# br__pl_power_adapter.net
KiCad netlist of a schematic drawn in Altium Designer
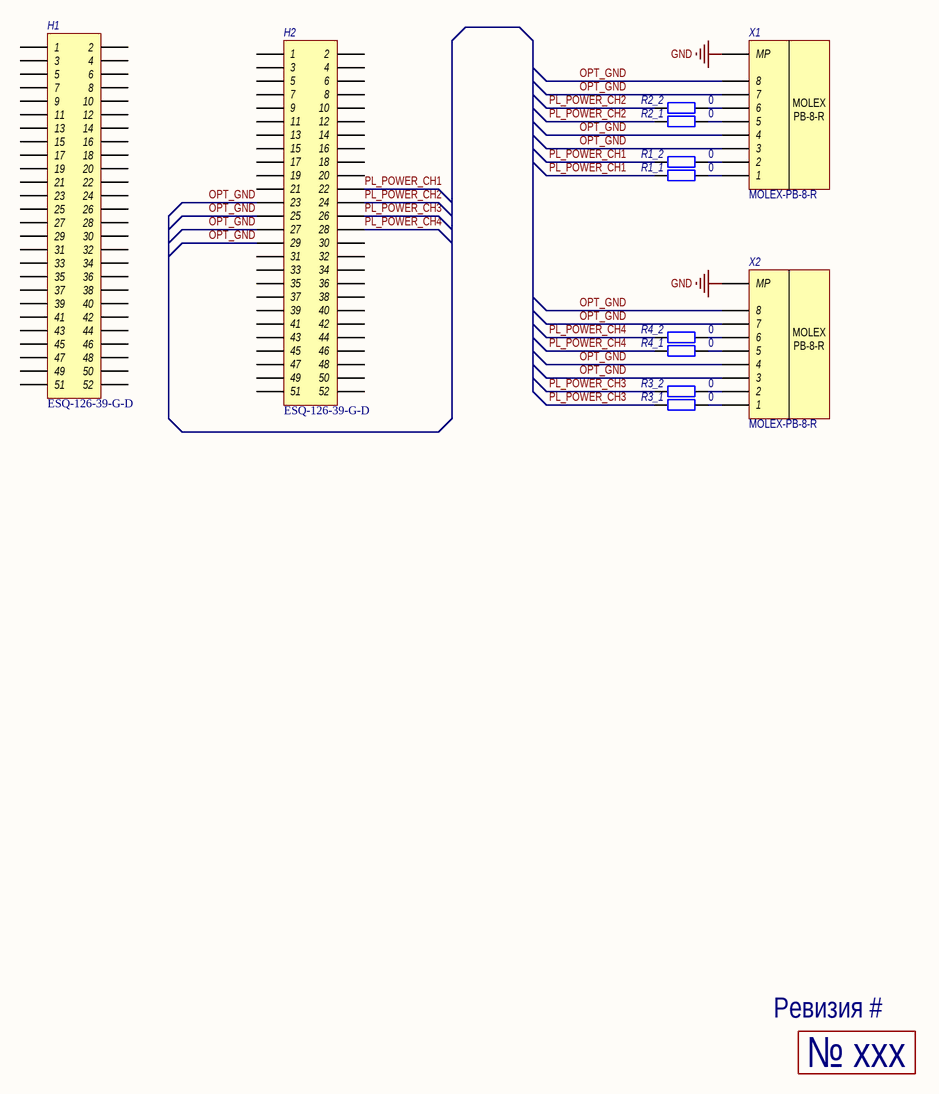
[diagram p0: brс_pl_power_adapter.SchDoc]

(export (version "E")
  (design (tool "Eeschema 10.0.6"))
  (components
    (comp (ref "H1")
      (value "ESQ-126-39-G-D")
      (footprint "ESQ-126-39-G-D")
      (description "Elevated socket, dual-row, 26-pin per row")
      (libsource (lib "ESQ-126-39-G-D") (part "ESQ-126-39-G-D"))
    )
    (comp (ref "H2")
      (value "ESQ-126-39-G-D")
      (footprint "ESQ-126-39-G-D")
      (description "Elevated socket, dual-row, 26-pin per row")
      (libsource (lib "ESQ-126-39-G-D") (part "ESQ-126-39-G-D"))
    )
    (comp (ref "R1_1")
      (value "0")
      (footprint "SMD_0805")
      (description "Resistor")
      (fields (field (name "Comment") "OSM R1-12"))
      (libsource (lib "altium-import") (part "root_0_Resistor_"))
    )
    (comp (ref "R1_2")
      (value "0")
      (footprint "SMD_0805")
      (description "Resistor")
      (fields (field (name "Comment") "OSM R1-12"))
      (libsource (lib "altium-import") (part "root_0_Resistor_"))
    )
    (comp (ref "R2_1")
      (value "0")
      (footprint "SMD_0805")
      (description "Resistor")
      (fields (field (name "Comment") "OSM R1-12"))
      (libsource (lib "altium-import") (part "root_0_Resistor_"))
    )
    (comp (ref "R2_2")
      (value "0")
      (footprint "SMD_0805")
      (description "Resistor")
      (fields (field (name "Comment") "OSM R1-12"))
      (libsource (lib "altium-import") (part "root_0_Resistor_"))
    )
    (comp (ref "R3_1")
      (value "0")
      (footprint "SMD_0805")
      (description "Resistor")
      (fields (field (name "Comment") "OSM R1-12"))
      (libsource (lib "altium-import") (part "root_0_Resistor_"))
    )
    (comp (ref "R3_2")
      (value "0")
      (footprint "SMD_0805")
      (description "Resistor")
      (fields (field (name "Comment") "OSM R1-12"))
      (libsource (lib "altium-import") (part "root_0_Resistor_"))
    )
    (comp (ref "R4_1")
      (value "0")
      (footprint "SMD_0805")
      (description "Resistor")
      (fields (field (name "Comment") "OSM R1-12"))
      (libsource (lib "altium-import") (part "root_0_Resistor_"))
    )
    (comp (ref "R4_2")
      (value "0")
      (footprint "SMD_0805")
      (description "Resistor")
      (fields (field (name "Comment") "OSM R1-12"))
      (libsource (lib "altium-import") (part "root_0_Resistor_"))
    )
    (comp (ref "SN")
      (value "Место под нанесение серийного номера")
      (footprint "Serial_number_v3")
      (libsource (lib "altium-import") (part "root_0_Serial_number_"))
    )
    (comp (ref "X1")
      (value "MOLEX-PB-8")
      (footprint "MOLEX-PB-8-R")
      (description "MOLEX PicoBlade 8-pin")
      (fields (field (name "НАИМЕНОВАНИЕ") "MOLEX-PB-8-R"))
      (libsource (lib "Molex-PB-8") (part "MOLEX-PB-8"))
    )
    (comp (ref "X2")
      (value "MOLEX-PB-8")
      (footprint "MOLEX-PB-8-R")
      (description "MOLEX PicoBlade 8-pin")
      (fields (field (name "НАИМЕНОВАНИЕ") "MOLEX-PB-8-R"))
      (libsource (lib "Molex-PB-8") (part "MOLEX-PB-8"))
    )
  )
  (nets
    (net (code "1") (name "/OPT_GND") (class "Default")
      (node (ref "H2") (pin "23") (pinfunction "23_23") (pintype "passive"))
      (node (ref "H2") (pin "25") (pinfunction "25_25") (pintype "passive"))
      (node (ref "H2") (pin "27") (pinfunction "27_27") (pintype "passive"))
      (node (ref "H2") (pin "29") (pinfunction "29_29") (pintype "passive"))
      (node (ref "X1") (pin "3") (pinfunction "3_3") (pintype "passive"))
      (node (ref "X1") (pin "4") (pinfunction "4_4") (pintype "passive"))
      (node (ref "X1") (pin "7") (pinfunction "7_7") (pintype "passive"))
      (node (ref "X1") (pin "8") (pinfunction "8_8") (pintype "passive"))
      (node (ref "X2") (pin "3") (pinfunction "3_3") (pintype "passive"))
      (node (ref "X2") (pin "4") (pinfunction "4_4") (pintype "passive"))
      (node (ref "X2") (pin "7") (pinfunction "7_7") (pintype "passive"))
      (node (ref "X2") (pin "8") (pinfunction "8_8") (pintype "passive"))
    )
    (net (code "2") (name "/PL_POWER_CH1") (class "Default")
      (node (ref "H2") (pin "22") (pinfunction "22_22") (pintype "passive"))
      (node (ref "R1_1") (pin "1") (pinfunction "1_1") (pintype "passive"))
      (node (ref "R1_2") (pin "1") (pinfunction "1_1") (pintype "passive"))
    )
    (net (code "3") (name "/PL_POWER_CH2") (class "Default")
      (node (ref "H2") (pin "24") (pinfunction "24_24") (pintype "passive"))
      (node (ref "R2_1") (pin "1") (pinfunction "1_1") (pintype "passive"))
      (node (ref "R2_2") (pin "1") (pinfunction "1_1") (pintype "passive"))
    )
    (net (code "4") (name "/PL_POWER_CH3") (class "Default")
      (node (ref "H2") (pin "26") (pinfunction "26_26") (pintype "passive"))
      (node (ref "R3_1") (pin "1") (pinfunction "1_1") (pintype "passive"))
      (node (ref "R3_2") (pin "1") (pinfunction "1_1") (pintype "passive"))
    )
    (net (code "5") (name "/PL_POWER_CH4") (class "Default")
      (node (ref "H2") (pin "28") (pinfunction "28_28") (pintype "passive"))
      (node (ref "R4_1") (pin "1") (pinfunction "1_1") (pintype "passive"))
      (node (ref "R4_2") (pin "1") (pinfunction "1_1") (pintype "passive"))
    )
    (net (code "6") (name "GND") (class "Default")
      (node (ref "X1") (pin "MP") (pinfunction "MP_MP") (pintype "passive"))
      (node (ref "X2") (pin "MP") (pinfunction "MP_MP") (pintype "passive"))
    )
    (net (code "7") (name "Net-(R1_1-Pad2)") (class "Default")
      (node (ref "R1_1") (pin "2") (pinfunction "2_2") (pintype "passive"))
      (node (ref "X1") (pin "1") (pinfunction "1_1") (pintype "passive"))
    )
    (net (code "8") (name "Net-(R1_2-Pad2)") (class "Default")
      (node (ref "R1_2") (pin "2") (pinfunction "2_2") (pintype "passive"))
      (node (ref "X1") (pin "2") (pinfunction "2_2") (pintype "passive"))
    )
    (net (code "9") (name "Net-(R2_1-Pad2)") (class "Default")
      (node (ref "R2_1") (pin "2") (pinfunction "2_2") (pintype "passive"))
      (node (ref "X1") (pin "5") (pinfunction "5_5") (pintype "passive"))
    )
    (net (code "10") (name "Net-(R2_2-Pad2)") (class "Default")
      (node (ref "R2_2") (pin "2") (pinfunction "2_2") (pintype "passive"))
      (node (ref "X1") (pin "6") (pinfunction "6_6") (pintype "passive"))
    )
    (net (code "11") (name "Net-(R3_1-Pad2)") (class "Default")
      (node (ref "R3_1") (pin "2") (pinfunction "2_2") (pintype "passive"))
      (node (ref "X2") (pin "1") (pinfunction "1_1") (pintype "passive"))
    )
    (net (code "12") (name "Net-(R3_2-Pad2)") (class "Default")
      (node (ref "R3_2") (pin "2") (pinfunction "2_2") (pintype "passive"))
      (node (ref "X2") (pin "2") (pinfunction "2_2") (pintype "passive"))
    )
    (net (code "13") (name "Net-(R4_1-Pad2)") (class "Default")
      (node (ref "R4_1") (pin "2") (pinfunction "2_2") (pintype "passive"))
      (node (ref "X2") (pin "5") (pinfunction "5_5") (pintype "passive"))
    )
    (net (code "14") (name "Net-(R4_2-Pad2)") (class "Default")
      (node (ref "R4_2") (pin "2") (pinfunction "2_2") (pintype "passive"))
      (node (ref "X2") (pin "6") (pinfunction "6_6") (pintype "passive"))
    )
    (net (code "15") (name "unconnected-(H1-Pad1)") (class "Default")
      (node (ref "H1") (pin "1") (pinfunction "1_1") (pintype "passive"))
    )
    (net (code "16") (name "unconnected-(H1-Pad2)") (class "Default")
      (node (ref "H1") (pin "2") (pinfunction "2_2") (pintype "passive"))
    )
    (net (code "17") (name "unconnected-(H1-Pad3)") (class "Default")
      (node (ref "H1") (pin "3") (pinfunction "3_3") (pintype "passive"))
    )
    (net (code "18") (name "unconnected-(H1-Pad4)") (class "Default")
      (node (ref "H1") (pin "4") (pinfunction "4_4") (pintype "passive"))
    )
    (net (code "19") (name "unconnected-(H1-Pad5)") (class "Default")
      (node (ref "H1") (pin "5") (pinfunction "5_5") (pintype "passive"))
    )
    (net (code "20") (name "unconnected-(H1-Pad6)") (class "Default")
      (node (ref "H1") (pin "6") (pinfunction "6_6") (pintype "passive"))
    )
    (net (code "21") (name "unconnected-(H1-Pad7)") (class "Default")
      (node (ref "H1") (pin "7") (pinfunction "7_7") (pintype "passive"))
    )
    (net (code "22") (name "unconnected-(H1-Pad8)") (class "Default")
      (node (ref "H1") (pin "8") (pinfunction "8_8") (pintype "passive"))
    )
    (net (code "23") (name "unconnected-(H1-Pad9)") (class "Default")
      (node (ref "H1") (pin "9") (pinfunction "9_9") (pintype "passive"))
    )
    (net (code "24") (name "unconnected-(H1-Pad10)") (class "Default")
      (node (ref "H1") (pin "10") (pinfunction "10_10") (pintype "passive"))
    )
    (net (code "25") (name "unconnected-(H1-Pad11)") (class "Default")
      (node (ref "H1") (pin "11") (pinfunction "11_11") (pintype "passive"))
    )
    (net (code "26") (name "unconnected-(H1-Pad12)") (class "Default")
      (node (ref "H1") (pin "12") (pinfunction "12_12") (pintype "passive"))
    )
    (net (code "27") (name "unconnected-(H1-Pad13)") (class "Default")
      (node (ref "H1") (pin "13") (pinfunction "13_13") (pintype "passive"))
    )
    (net (code "28") (name "unconnected-(H1-Pad14)") (class "Default")
      (node (ref "H1") (pin "14") (pinfunction "14_14") (pintype "passive"))
    )
    (net (code "29") (name "unconnected-(H1-Pad15)") (class "Default")
      (node (ref "H1") (pin "15") (pinfunction "15_15") (pintype "passive"))
    )
    (net (code "30") (name "unconnected-(H1-Pad16)") (class "Default")
      (node (ref "H1") (pin "16") (pinfunction "16_16") (pintype "passive"))
    )
    (net (code "31") (name "unconnected-(H1-Pad17)") (class "Default")
      (node (ref "H1") (pin "17") (pinfunction "17_17") (pintype "passive"))
    )
    (net (code "32") (name "unconnected-(H1-Pad18)") (class "Default")
      (node (ref "H1") (pin "18") (pinfunction "18_18") (pintype "passive"))
    )
    (net (code "33") (name "unconnected-(H1-Pad19)") (class "Default")
      (node (ref "H1") (pin "19") (pinfunction "19_19") (pintype "passive"))
    )
    (net (code "34") (name "unconnected-(H1-Pad20)") (class "Default")
      (node (ref "H1") (pin "20") (pinfunction "20_20") (pintype "passive"))
    )
    (net (code "35") (name "unconnected-(H1-Pad21)") (class "Default")
      (node (ref "H1") (pin "21") (pinfunction "21_21") (pintype "passive"))
    )
    (net (code "36") (name "unconnected-(H1-Pad22)") (class "Default")
      (node (ref "H1") (pin "22") (pinfunction "22_22") (pintype "passive"))
    )
    (net (code "37") (name "unconnected-(H1-Pad23)") (class "Default")
      (node (ref "H1") (pin "23") (pinfunction "23_23") (pintype "passive"))
    )
    (net (code "38") (name "unconnected-(H1-Pad24)") (class "Default")
      (node (ref "H1") (pin "24") (pinfunction "24_24") (pintype "passive"))
    )
    (net (code "39") (name "unconnected-(H1-Pad25)") (class "Default")
      (node (ref "H1") (pin "25") (pinfunction "25_25") (pintype "passive"))
    )
    (net (code "40") (name "unconnected-(H1-Pad26)") (class "Default")
      (node (ref "H1") (pin "26") (pinfunction "26_26") (pintype "passive"))
    )
    (net (code "41") (name "unconnected-(H1-Pad27)") (class "Default")
      (node (ref "H1") (pin "27") (pinfunction "27_27") (pintype "passive"))
    )
    (net (code "42") (name "unconnected-(H1-Pad28)") (class "Default")
      (node (ref "H1") (pin "28") (pinfunction "28_28") (pintype "passive"))
    )
    (net (code "43") (name "unconnected-(H1-Pad29)") (class "Default")
      (node (ref "H1") (pin "29") (pinfunction "29_29") (pintype "passive"))
    )
    (net (code "44") (name "unconnected-(H1-Pad30)") (class "Default")
      (node (ref "H1") (pin "30") (pinfunction "30_30") (pintype "passive"))
    )
    (net (code "45") (name "unconnected-(H1-Pad31)") (class "Default")
      (node (ref "H1") (pin "31") (pinfunction "31_31") (pintype "passive"))
    )
    (net (code "46") (name "unconnected-(H1-Pad32)") (class "Default")
      (node (ref "H1") (pin "32") (pinfunction "32_32") (pintype "passive"))
    )
    (net (code "47") (name "unconnected-(H1-Pad33)") (class "Default")
      (node (ref "H1") (pin "33") (pinfunction "33_33") (pintype "passive"))
    )
    (net (code "48") (name "unconnected-(H1-Pad34)") (class "Default")
      (node (ref "H1") (pin "34") (pinfunction "34_34") (pintype "passive"))
    )
    (net (code "49") (name "unconnected-(H1-Pad35)") (class "Default")
      (node (ref "H1") (pin "35") (pinfunction "35_35") (pintype "passive"))
    )
    (net (code "50") (name "unconnected-(H1-Pad36)") (class "Default")
      (node (ref "H1") (pin "36") (pinfunction "36_36") (pintype "passive"))
    )
    (net (code "51") (name "unconnected-(H1-Pad37)") (class "Default")
      (node (ref "H1") (pin "37") (pinfunction "37_37") (pintype "passive"))
    )
    (net (code "52") (name "unconnected-(H1-Pad38)") (class "Default")
      (node (ref "H1") (pin "38") (pinfunction "38_38") (pintype "passive"))
    )
    (net (code "53") (name "unconnected-(H1-Pad39)") (class "Default")
      (node (ref "H1") (pin "39") (pinfunction "39_39") (pintype "passive"))
    )
    (net (code "54") (name "unconnected-(H1-Pad40)") (class "Default")
      (node (ref "H1") (pin "40") (pinfunction "40_40") (pintype "passive"))
    )
    (net (code "55") (name "unconnected-(H1-Pad41)") (class "Default")
      (node (ref "H1") (pin "41") (pinfunction "41_41") (pintype "passive"))
    )
    (net (code "56") (name "unconnected-(H1-Pad42)") (class "Default")
      (node (ref "H1") (pin "42") (pinfunction "42_42") (pintype "passive"))
    )
    (net (code "57") (name "unconnected-(H1-Pad43)") (class "Default")
      (node (ref "H1") (pin "43") (pinfunction "43_43") (pintype "passive"))
    )
    (net (code "58") (name "unconnected-(H1-Pad44)") (class "Default")
      (node (ref "H1") (pin "44") (pinfunction "44_44") (pintype "passive"))
    )
    (net (code "59") (name "unconnected-(H1-Pad45)") (class "Default")
      (node (ref "H1") (pin "45") (pinfunction "45_45") (pintype "passive"))
    )
    (net (code "60") (name "unconnected-(H1-Pad46)") (class "Default")
      (node (ref "H1") (pin "46") (pinfunction "46_46") (pintype "passive"))
    )
    (net (code "61") (name "unconnected-(H1-Pad47)") (class "Default")
      (node (ref "H1") (pin "47") (pinfunction "47_47") (pintype "passive"))
    )
    (net (code "62") (name "unconnected-(H1-Pad48)") (class "Default")
      (node (ref "H1") (pin "48") (pinfunction "48_48") (pintype "passive"))
    )
    (net (code "63") (name "unconnected-(H1-Pad49)") (class "Default")
      (node (ref "H1") (pin "49") (pinfunction "49_49") (pintype "passive"))
    )
    (net (code "64") (name "unconnected-(H1-Pad50)") (class "Default")
      (node (ref "H1") (pin "50") (pinfunction "50_50") (pintype "passive"))
    )
    (net (code "65") (name "unconnected-(H1-Pad51)") (class "Default")
      (node (ref "H1") (pin "51") (pinfunction "51_51") (pintype "passive"))
    )
    (net (code "66") (name "unconnected-(H1-Pad52)") (class "Default")
      (node (ref "H1") (pin "52") (pinfunction "52_52") (pintype "passive"))
    )
    (net (code "67") (name "unconnected-(H2-Pad1)") (class "Default")
      (node (ref "H2") (pin "1") (pinfunction "1_1") (pintype "passive"))
    )
    (net (code "68") (name "unconnected-(H2-Pad2)") (class "Default")
      (node (ref "H2") (pin "2") (pinfunction "2_2") (pintype "passive"))
    )
    (net (code "69") (name "unconnected-(H2-Pad3)") (class "Default")
      (node (ref "H2") (pin "3") (pinfunction "3_3") (pintype "passive"))
    )
    (net (code "70") (name "unconnected-(H2-Pad4)") (class "Default")
      (node (ref "H2") (pin "4") (pinfunction "4_4") (pintype "passive"))
    )
    (net (code "71") (name "unconnected-(H2-Pad5)") (class "Default")
      (node (ref "H2") (pin "5") (pinfunction "5_5") (pintype "passive"))
    )
    (net (code "72") (name "unconnected-(H2-Pad6)") (class "Default")
      (node (ref "H2") (pin "6") (pinfunction "6_6") (pintype "passive"))
    )
    (net (code "73") (name "unconnected-(H2-Pad7)") (class "Default")
      (node (ref "H2") (pin "7") (pinfunction "7_7") (pintype "passive"))
    )
    (net (code "74") (name "unconnected-(H2-Pad8)") (class "Default")
      (node (ref "H2") (pin "8") (pinfunction "8_8") (pintype "passive"))
    )
    (net (code "75") (name "unconnected-(H2-Pad9)") (class "Default")
      (node (ref "H2") (pin "9") (pinfunction "9_9") (pintype "passive"))
    )
    (net (code "76") (name "unconnected-(H2-Pad10)") (class "Default")
      (node (ref "H2") (pin "10") (pinfunction "10_10") (pintype "passive"))
    )
    (net (code "77") (name "unconnected-(H2-Pad11)") (class "Default")
      (node (ref "H2") (pin "11") (pinfunction "11_11") (pintype "passive"))
    )
    (net (code "78") (name "unconnected-(H2-Pad12)") (class "Default")
      (node (ref "H2") (pin "12") (pinfunction "12_12") (pintype "passive"))
    )
    (net (code "79") (name "unconnected-(H2-Pad13)") (class "Default")
      (node (ref "H2") (pin "13") (pinfunction "13_13") (pintype "passive"))
    )
    (net (code "80") (name "unconnected-(H2-Pad14)") (class "Default")
      (node (ref "H2") (pin "14") (pinfunction "14_14") (pintype "passive"))
    )
    (net (code "81") (name "unconnected-(H2-Pad15)") (class "Default")
      (node (ref "H2") (pin "15") (pinfunction "15_15") (pintype "passive"))
    )
    (net (code "82") (name "unconnected-(H2-Pad16)") (class "Default")
      (node (ref "H2") (pin "16") (pinfunction "16_16") (pintype "passive"))
    )
    (net (code "83") (name "unconnected-(H2-Pad17)") (class "Default")
      (node (ref "H2") (pin "17") (pinfunction "17_17") (pintype "passive"))
    )
    (net (code "84") (name "unconnected-(H2-Pad18)") (class "Default")
      (node (ref "H2") (pin "18") (pinfunction "18_18") (pintype "passive"))
    )
    (net (code "85") (name "unconnected-(H2-Pad19)") (class "Default")
      (node (ref "H2") (pin "19") (pinfunction "19_19") (pintype "passive"))
    )
    (net (code "86") (name "unconnected-(H2-Pad20)") (class "Default")
      (node (ref "H2") (pin "20") (pinfunction "20_20") (pintype "passive"))
    )
    (net (code "87") (name "unconnected-(H2-Pad21)") (class "Default")
      (node (ref "H2") (pin "21") (pinfunction "21_21") (pintype "passive"))
    )
    (net (code "88") (name "unconnected-(H2-Pad30)") (class "Default")
      (node (ref "H2") (pin "30") (pinfunction "30_30") (pintype "passive"))
    )
    (net (code "89") (name "unconnected-(H2-Pad31)") (class "Default")
      (node (ref "H2") (pin "31") (pinfunction "31_31") (pintype "passive"))
    )
    (net (code "90") (name "unconnected-(H2-Pad32)") (class "Default")
      (node (ref "H2") (pin "32") (pinfunction "32_32") (pintype "passive"))
    )
    (net (code "91") (name "unconnected-(H2-Pad33)") (class "Default")
      (node (ref "H2") (pin "33") (pinfunction "33_33") (pintype "passive"))
    )
    (net (code "92") (name "unconnected-(H2-Pad34)") (class "Default")
      (node (ref "H2") (pin "34") (pinfunction "34_34") (pintype "passive"))
    )
    (net (code "93") (name "unconnected-(H2-Pad35)") (class "Default")
      (node (ref "H2") (pin "35") (pinfunction "35_35") (pintype "passive"))
    )
    (net (code "94") (name "unconnected-(H2-Pad36)") (class "Default")
      (node (ref "H2") (pin "36") (pinfunction "36_36") (pintype "passive"))
    )
    (net (code "95") (name "unconnected-(H2-Pad37)") (class "Default")
      (node (ref "H2") (pin "37") (pinfunction "37_37") (pintype "passive"))
    )
    (net (code "96") (name "unconnected-(H2-Pad38)") (class "Default")
      (node (ref "H2") (pin "38") (pinfunction "38_38") (pintype "passive"))
    )
    (net (code "97") (name "unconnected-(H2-Pad39)") (class "Default")
      (node (ref "H2") (pin "39") (pinfunction "39_39") (pintype "passive"))
    )
    (net (code "98") (name "unconnected-(H2-Pad40)") (class "Default")
      (node (ref "H2") (pin "40") (pinfunction "40_40") (pintype "passive"))
    )
    (net (code "99") (name "unconnected-(H2-Pad41)") (class "Default")
      (node (ref "H2") (pin "41") (pinfunction "41_41") (pintype "passive"))
    )
    (net (code "100") (name "unconnected-(H2-Pad42)") (class "Default")
      (node (ref "H2") (pin "42") (pinfunction "42_42") (pintype "passive"))
    )
    (net (code "101") (name "unconnected-(H2-Pad43)") (class "Default")
      (node (ref "H2") (pin "43") (pinfunction "43_43") (pintype "passive"))
    )
    (net (code "102") (name "unconnected-(H2-Pad44)") (class "Default")
      (node (ref "H2") (pin "44") (pinfunction "44_44") (pintype "passive"))
    )
    (net (code "103") (name "unconnected-(H2-Pad45)") (class "Default")
      (node (ref "H2") (pin "45") (pinfunction "45_45") (pintype "passive"))
    )
    (net (code "104") (name "unconnected-(H2-Pad46)") (class "Default")
      (node (ref "H2") (pin "46") (pinfunction "46_46") (pintype "passive"))
    )
    (net (code "105") (name "unconnected-(H2-Pad47)") (class "Default")
      (node (ref "H2") (pin "47") (pinfunction "47_47") (pintype "passive"))
    )
    (net (code "106") (name "unconnected-(H2-Pad48)") (class "Default")
      (node (ref "H2") (pin "48") (pinfunction "48_48") (pintype "passive"))
    )
    (net (code "107") (name "unconnected-(H2-Pad49)") (class "Default")
      (node (ref "H2") (pin "49") (pinfunction "49_49") (pintype "passive"))
    )
    (net (code "108") (name "unconnected-(H2-Pad50)") (class "Default")
      (node (ref "H2") (pin "50") (pinfunction "50_50") (pintype "passive"))
    )
    (net (code "109") (name "unconnected-(H2-Pad51)") (class "Default")
      (node (ref "H2") (pin "51") (pinfunction "51_51") (pintype "passive"))
    )
    (net (code "110") (name "unconnected-(H2-Pad52)") (class "Default")
      (node (ref "H2") (pin "52") (pinfunction "52_52") (pintype "passive"))
    )
  )
)
